# FOC_DRV8323.net
KiCad netlist of a schematic drawn in Altium Designer
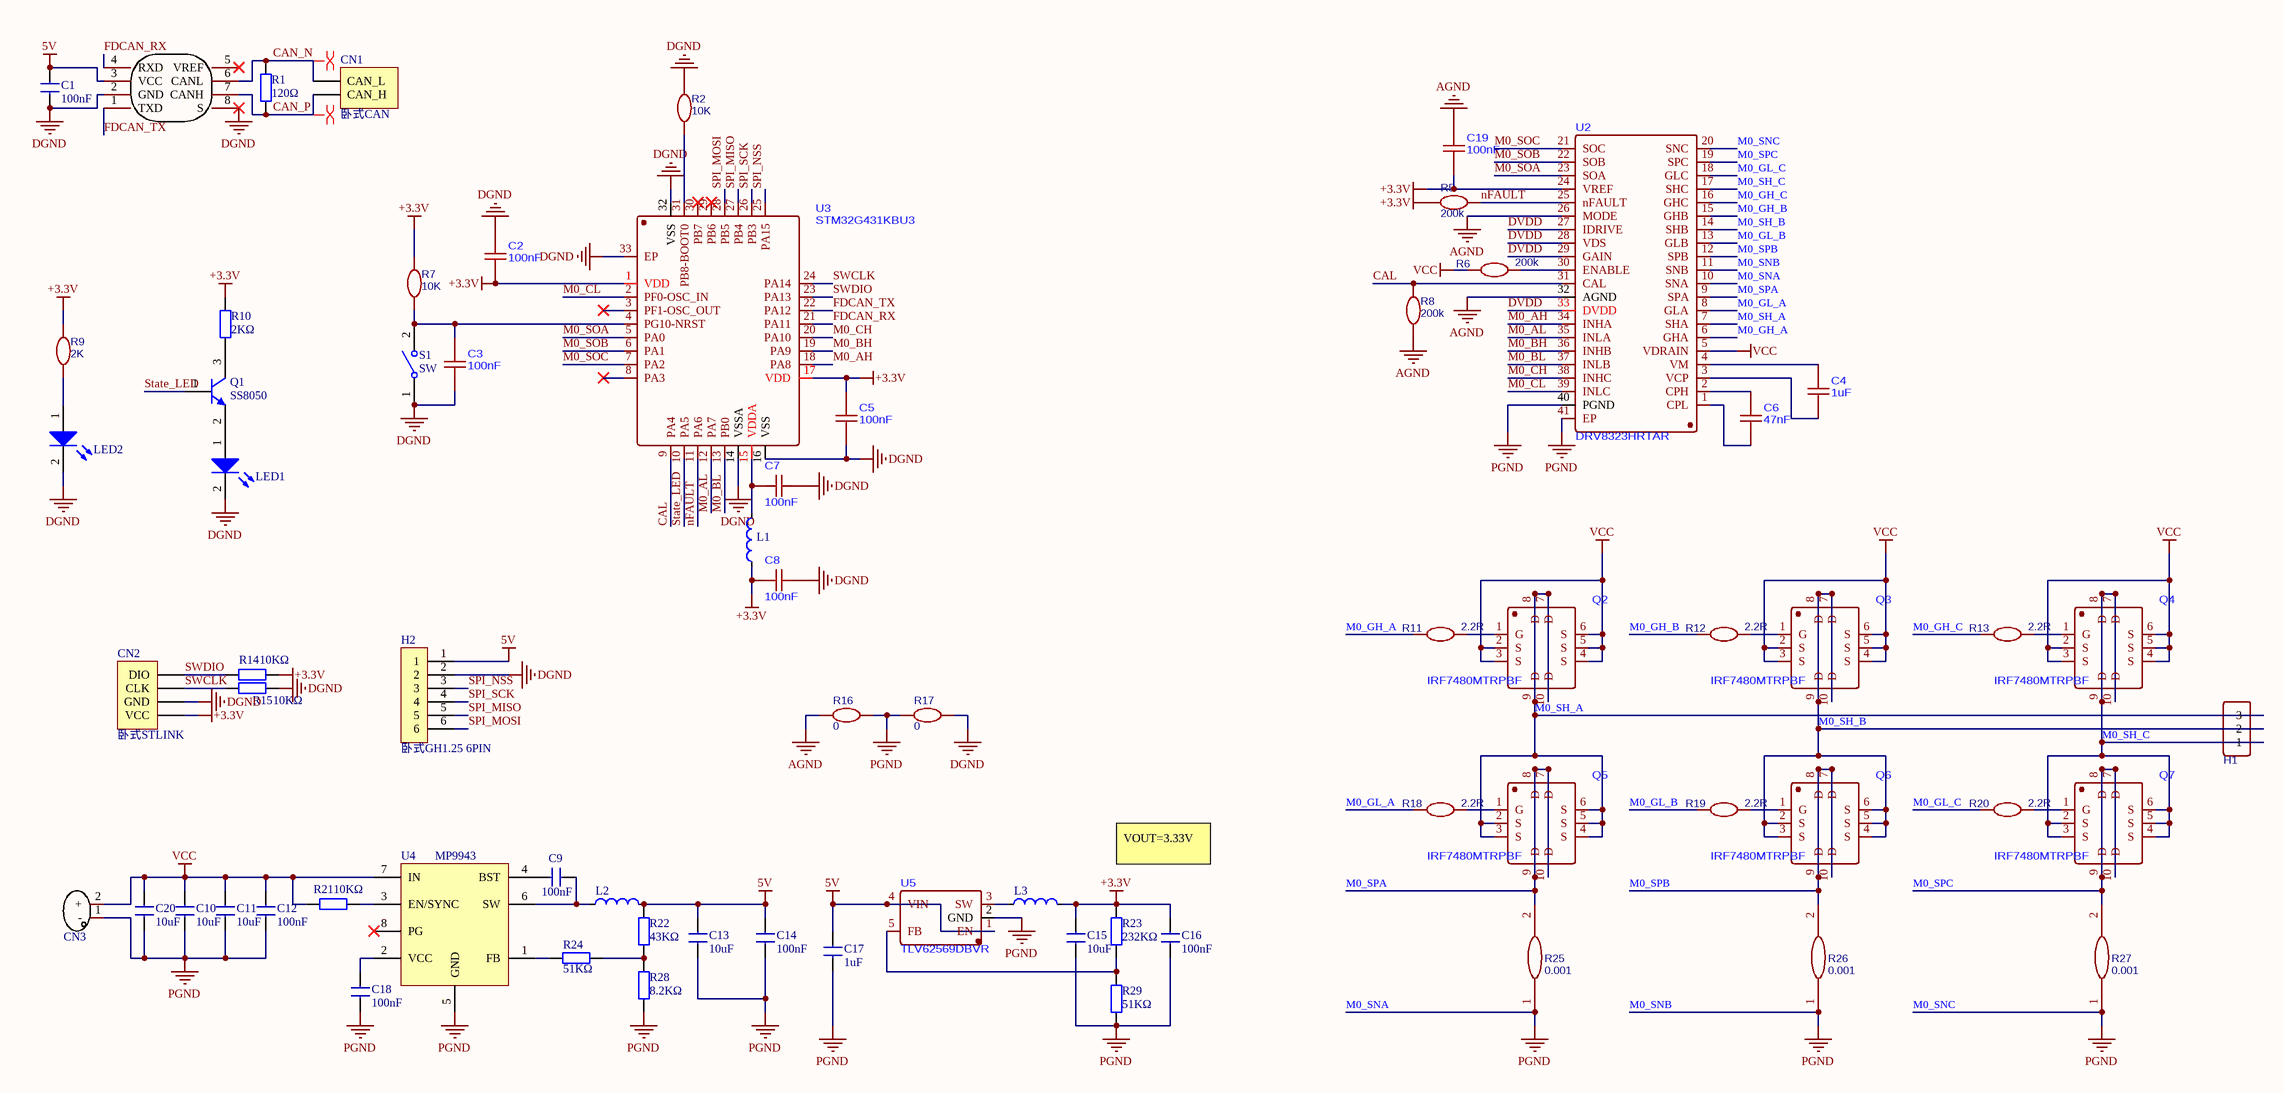
[diagram p0: FOC_DRV8323.SchDoc]

(export (version "E")
  (design (tool "Eeschema 10.0.6"))
  (components
    (comp (ref "C1")
      (value "100nF")
      (footprint "c0402")
      (description "贴片电容0402")
      (libsource (lib "Integrated_Library1") (part "0402贴片电容"))
    )
    (comp (ref "C2") (value "100nF") (footprint "c0402") (libsource (lib "PETO") (part "CC0201JRX7R9BB101")))
    (comp (ref "C3") (value "100nF") (footprint "c0402") (libsource (lib "PETO") (part "CC0201JRX7R9BB101")))
    (comp (ref "C4") (value "1uF") (footprint "c0402") (libsource (lib "PETO") (part "CC0201JRX7R9BB101")))
    (comp (ref "C5") (value "100nF") (footprint "c0402") (libsource (lib "PETO") (part "CC0201JRX7R9BB101")))
    (comp (ref "C6") (value "47nF") (footprint "c0402") (libsource (lib "PETO") (part "CC0201JRX7R9BB101")))
    (comp (ref "C7") (value "100nF") (footprint "c0402") (libsource (lib "PETO") (part "CC0201JRX7R9BB101")))
    (comp (ref "C8") (value "100nF") (footprint "c0402") (libsource (lib "PETO") (part "CC0201JRX7R9BB101")))
    (comp (ref "C9")
      (value "100nF")
      (footprint "c0402")
      (description "贴片电容0402")
      (libsource (lib "Integrated_Library1") (part "0402贴片电容"))
    )
    (comp (ref "C10")
      (value "10uF")
      (footprint "1210")
      (description "1210贴片电容")
      (libsource (lib "Integrated_Library1") (part "1210贴片电容"))
    )
    (comp (ref "C11")
      (value "10uF")
      (footprint "1210")
      (description "1210贴片电容")
      (libsource (lib "Integrated_Library1") (part "1210贴片电容"))
    )
    (comp (ref "C12")
      (value "100nF")
      (footprint "c0402")
      (description "贴片电容0402")
      (libsource (lib "Integrated_Library1") (part "0402贴片电容"))
    )
    (comp (ref "C13")
      (value "10uF")
      (footprint "1210")
      (description "1210贴片电容")
      (libsource (lib "Integrated_Library1") (part "1210贴片电容"))
    )
    (comp (ref "C14")
      (value "100nF")
      (footprint "c0402")
      (description "贴片电容0402")
      (libsource (lib "Integrated_Library1") (part "0402贴片电容"))
    )
    (comp (ref "C15")
      (value "10uF")
      (footprint "1210")
      (description "贴片电容0402")
      (libsource (lib "Integrated_Library1") (part "0402贴片电容"))
    )
    (comp (ref "C16")
      (value "100nF")
      (footprint "c0402")
      (description "贴片电容0402")
      (libsource (lib "Integrated_Library1") (part "0402贴片电容"))
    )
    (comp (ref "C17")
      (value "1uF")
      (footprint "c0402")
      (description "贴片电容0402")
      (libsource (lib "Integrated_Library1") (part "0402贴片电容"))
    )
    (comp (ref "C18")
      (value "100nF")
      (footprint "c0402")
      (description "贴片电容0402")
      (libsource (lib "Integrated_Library1") (part "0402贴片电容"))
    )
    (comp (ref "C19") (value "100nF") (footprint "c0402") (libsource (lib "PETO") (part "CC0201JRX7R9BB101")))
    (comp (ref "C20")
      (value "10uF")
      (footprint "1210")
      (description "1210贴片电容")
      (libsource (lib "Integrated_Library1") (part "1210贴片电容"))
    )
    (comp (ref "CN1")
      (value "卧式CAN")
      (footprint "GH1.25 2P 卧式")
      (fields (field (name "PUBLISHER") "Altium Limited"))
      (libsource (lib "Integrated_Library1") (part "卧式CAN"))
    )
    (comp (ref "CN2")
      (value "卧式STLINK")
      (footprint "CONN-SMD_4P-P1.25_GH1.25-4P")
      (libsource (lib "Integrated_Library1") (part "卧式STLINK"))
    )
    (comp (ref "CN3") (value "XT30_1") (footprint "XT30卧式焊盘") (libsource (lib "Schlib1") (part "XT30_1")))
    (comp (ref "H1")
      (value "MR30-M")
      (footprint "MR30")
      (fields (field (name "BOM_SUPPLIER PART") "C99873") (field (name "CONTRIBUTOR") "LCEDA_Lib"))
      (libsource (lib "altium-import") (part "root_2_MR30-M_"))
    )
    (comp (ref "H2")
      (value "卧式GH1.25 6PIN")
      (footprint "CONN-SMD_6P-P1.25_XYECONN_XY-GH1.25-6A61")
      (libsource (lib "En") (part "卧式GH1.25 6PIN"))
    )
    (comp (ref "L1")
      (value "1008屏蔽电感")
      (footprint "R0603")
      (libsource (lib "Integrated_Library1") (part "1008屏蔽电感"))
    )
    (comp (ref "L2")
      (value "1008屏蔽电感")
      (footprint "IND-SMD_L2.5-W2.0")
      (libsource (lib "Integrated_Library1") (part "1008屏蔽电感"))
    )
    (comp (ref "L3")
      (value "1008屏蔽电感")
      (footprint "IND-SMD_L2.5-W2.0")
      (libsource (lib "Integrated_Library1") (part "1008屏蔽电感"))
    )
    (comp (ref "LED1")
      (value "LED")
      (footprint "led0805")
      (description "0805贴片LED")
      (libsource (lib "Integrated_Library1") (part "0805贴片LED"))
    )
    (comp (ref "LED2")
      (value "LED")
      (footprint "led0805")
      (description "0805贴片LED")
      (libsource (lib "Integrated_Library1") (part "0805贴片LED"))
    )
    (comp (ref "Q1")
      (value "SS8050")
      (footprint "SOT-23-3_L2.9-W1.3-P1.90-LS2.4-BR")
      (description "三极管")
      (libsource (lib "Integrated_Library1") (part "2N2222"))
    )
    (comp (ref "Q2")
      (value "IRF7480MTRPBF")
      (footprint "TRS-SMD_IRF7480MTRPBF")
      (libsource (lib "FOC_DRV8301") (part "IRF7480MTRPBF"))
    )
    (comp (ref "Q3")
      (value "IRF7480MTRPBF")
      (footprint "TRS-SMD_IRF7480MTRPBF")
      (libsource (lib "FOC_DRV8301") (part "IRF7480MTRPBF"))
    )
    (comp (ref "Q4")
      (value "IRF7480MTRPBF")
      (footprint "TRS-SMD_IRF7480MTRPBF")
      (libsource (lib "FOC_DRV8301") (part "IRF7480MTRPBF"))
    )
    (comp (ref "Q5")
      (value "IRF7480MTRPBF")
      (footprint "TRS-SMD_IRF7480MTRPBF")
      (libsource (lib "FOC_DRV8301") (part "IRF7480MTRPBF"))
    )
    (comp (ref "Q6")
      (value "IRF7480MTRPBF")
      (footprint "TRS-SMD_IRF7480MTRPBF")
      (libsource (lib "FOC_DRV8301") (part "IRF7480MTRPBF"))
    )
    (comp (ref "Q7")
      (value "IRF7480MTRPBF")
      (footprint "TRS-SMD_IRF7480MTRPBF")
      (libsource (lib "FOC_DRV8301") (part "IRF7480MTRPBF"))
    )
    (comp (ref "R1")
      (value "120Ω")
      (footprint "R0402")
      (description "0402贴片电阻")
      (libsource (lib "Integrated_Library1") (part "0402贴片电阻"))
    )
    (comp (ref "R2")
      (value "10K")
      (footprint "R0402")
      (fields
        (field (name "BOM_MANUFACTURER PART") "0603WAJ022JT5E")
        (field (name "BOM_SUPPLIER PART") "C25226")
      )
      (libsource (lib "altium-import") (part "root_3_2.2R_"))
    )
    (comp (ref "R5")
      (value "200k")
      (footprint "R0402")
      (fields
        (field (name "BOM_MANUFACTURER PART") "0603WAJ022JT5E")
        (field (name "BOM_SUPPLIER PART") "C25226")
      )
      (libsource (lib "altium-import") (part "root_0_2.2R_"))
    )
    (comp (ref "R6")
      (value "200k")
      (footprint "R0402")
      (fields
        (field (name "BOM_MANUFACTURER PART") "0603WAJ022JT5E")
        (field (name "BOM_SUPPLIER PART") "C25226")
      )
      (libsource (lib "altium-import") (part "root_2_2.2R_"))
    )
    (comp (ref "R7")
      (value "10K")
      (footprint "R0402")
      (fields
        (field (name "BOM_MANUFACTURER PART") "0603WAJ022JT5E")
        (field (name "BOM_SUPPLIER PART") "C25226")
      )
      (libsource (lib "altium-import") (part "root_3_2.2R_"))
    )
    (comp (ref "R8")
      (value "200k")
      (footprint "R0402")
      (fields
        (field (name "BOM_MANUFACTURER PART") "0603WAJ022JT5E")
        (field (name "BOM_SUPPLIER PART") "C25226")
      )
      (libsource (lib "altium-import") (part "root_3_2.2R_"))
    )
    (comp (ref "R9")
      (value "2K")
      (footprint "R0402")
      (fields
        (field (name "BOM_MANUFACTURER PART") "0603WAJ022JT5E")
        (field (name "BOM_SUPPLIER PART") "C25226")
      )
      (libsource (lib "altium-import") (part "root_3_2.2R_"))
    )
    (comp (ref "R10")
      (value "2KΩ")
      (footprint "R0402")
      (description "0402贴片电阻")
      (libsource (lib "Integrated_Library1") (part "0402贴片电阻"))
    )
    (comp (ref "R11")
      (value "2.2R")
      (footprint "R0402")
      (fields
        (field (name "BOM_MANUFACTURER PART") "0603WAJ022JT5E")
        (field (name "BOM_SUPPLIER PART") "C25226")
      )
      (libsource (lib "altium-import") (part "root_2_2.2R_"))
    )
    (comp (ref "R12")
      (value "2.2R")
      (footprint "R0402")
      (fields
        (field (name "BOM_MANUFACTURER PART") "0603WAJ022JT5E")
        (field (name "BOM_SUPPLIER PART") "C25226")
      )
      (libsource (lib "altium-import") (part "root_2_2.2R_"))
    )
    (comp (ref "R13")
      (value "2.2R")
      (footprint "R0402")
      (fields
        (field (name "BOM_MANUFACTURER PART") "0603WAJ022JT5E")
        (field (name "BOM_SUPPLIER PART") "C25226")
      )
      (libsource (lib "altium-import") (part "root_2_2.2R_"))
    )
    (comp (ref "R14")
      (value "10KΩ")
      (footprint "R0402")
      (description "0402贴片电阻")
      (libsource (lib "") (part "0402贴片电阻_4"))
    )
    (comp (ref "R15")
      (value "10KΩ")
      (footprint "R0402")
      (description "0402贴片电阻")
      (libsource (lib "") (part "0402贴片电阻_3"))
    )
    (comp (ref "R16")
      (value "0")
      (footprint "R0402")
      (fields
        (field (name "BOM_MANUFACTURER PART") "0603WAJ022JT5E")
        (field (name "BOM_SUPPLIER PART") "C25226")
      )
      (libsource (lib "altium-import") (part "root_0_2.2R_"))
    )
    (comp (ref "R17")
      (value "0")
      (footprint "R0402")
      (fields
        (field (name "BOM_MANUFACTURER PART") "0603WAJ022JT5E")
        (field (name "BOM_SUPPLIER PART") "C25226")
      )
      (libsource (lib "altium-import") (part "root_0_2.2R_"))
    )
    (comp (ref "R18")
      (value "2.2R")
      (footprint "R0402")
      (fields
        (field (name "BOM_MANUFACTURER PART") "0603WAJ022JT5E")
        (field (name "BOM_SUPPLIER PART") "C25226")
      )
      (libsource (lib "altium-import") (part "root_2_2.2R_"))
    )
    (comp (ref "R19")
      (value "2.2R")
      (footprint "R0402")
      (fields
        (field (name "BOM_MANUFACTURER PART") "0603WAJ022JT5E")
        (field (name "BOM_SUPPLIER PART") "C25226")
      )
      (libsource (lib "altium-import") (part "root_2_2.2R_"))
    )
    (comp (ref "R20")
      (value "2.2R")
      (footprint "R0402")
      (fields
        (field (name "BOM_MANUFACTURER PART") "0603WAJ022JT5E")
        (field (name "BOM_SUPPLIER PART") "C25226")
      )
      (libsource (lib "altium-import") (part "root_2_2.2R_"))
    )
    (comp (ref "R21")
      (value "10KΩ")
      (footprint "R0402")
      (description "0402贴片电阻")
      (libsource (lib "") (part "0402贴片电阻_2"))
    )
    (comp (ref "R22")
      (value "43KΩ")
      (footprint "R0402")
      (description "0402贴片电阻")
      (libsource (lib "") (part "0402贴片电阻_1"))
    )
    (comp (ref "R23")
      (value "232KΩ")
      (footprint "R0402")
      (description "0402贴片电阻")
      (libsource (lib "") (part "0402贴片电阻_1"))
    )
    (comp (ref "R24")
      (value "51KΩ")
      (footprint "R0402")
      (description "0402贴片电阻")
      (libsource (lib "") (part "0402贴片电阻_2"))
    )
    (comp (ref "R25")
      (value "0.001")
      (footprint "R0612")
      (fields
        (field (name "BOM_SUPPLIER PART") "C2681067")
        (field (name "BOM_MANUFACTURER PART") "LR2512-23R0005J4")
        (field (name "CONTRIBUTOR") "LCSC")
      )
      (libsource (lib "altium-import") (part "root_1_0.0005_"))
    )
    (comp (ref "R26")
      (value "0.001")
      (footprint "R0612")
      (fields
        (field (name "BOM_SUPPLIER PART") "C2681067")
        (field (name "BOM_MANUFACTURER PART") "LR2512-23R0005J4")
        (field (name "CONTRIBUTOR") "LCSC")
      )
      (libsource (lib "altium-import") (part "root_1_0.0005_"))
    )
    (comp (ref "R27")
      (value "0.001")
      (footprint "R0612")
      (fields
        (field (name "BOM_SUPPLIER PART") "C2681067")
        (field (name "BOM_MANUFACTURER PART") "LR2512-23R0005J4")
        (field (name "CONTRIBUTOR") "LCSC")
      )
      (libsource (lib "altium-import") (part "root_1_0.0005_"))
    )
    (comp (ref "R28")
      (value "8.2KΩ")
      (footprint "R0402")
      (description "0402贴片电阻")
      (libsource (lib "") (part "0402贴片电阻_1"))
    )
    (comp (ref "R29")
      (value "51KΩ")
      (footprint "R0402")
      (description "0402贴片电阻")
      (libsource (lib "") (part "0402贴片电阻_1"))
    )
    (comp (ref "S1")
      (value "SW")
      (footprint "KEY_SMD")
      (description "开关")
      (libsource (lib "Integrated_Library1") (part "SW"))
    )
    (comp (ref "U1")
      (value "SN65HVD1050DR")
      (footprint "SOIC-8_L4.9-W3.9-P1.27-LS6.0-BL")
      (description "CAN芯片")
      (fields (field (name "MANUFACTURER") "TI(德州仪器)"))
      (libsource (lib "Integrated_Library1") (part "SN65HVD1050DR"))
    )
    (comp (ref "U2")
      (value "DRV8323HRTAR")
      (footprint "QFN-40_L6.0-W6.0-P0.50-BL-EP4.5")
      (libsource (lib "FOC_DRV8323") (part "DRV8323HRTAR"))
    )
    (comp (ref "U3")
      (value "STM32G431KBU3")
      (footprint "UFQFPN-32_L5.0-W5.0-P0.50-BL-EP3.5")
      (libsource (lib "FOC_DRV8323") (part "STM32G431KBU3"))
    )
    (comp (ref "U4")
      (value "MP9943")
      (footprint "QFN-8 3x3")
      (libsource (lib "Integrated_Library1") (part "MP9943"))
    )
    (comp (ref "U5")
      (value "TLV62569DBVR")
      (footprint "SOT-23-5_L3.0-W1.7-P0.95-LS2.8-BR")
      (libsource (lib "FOC_DRV8323") (part "TLV62569DBVR"))
    )
  )
  (nets
    (net (code "1") (name "+3.3V") (class "Default")
      (node (ref "C15") (pin "2") (pinfunction "2_2") (pintype "passive"))
      (node (ref "C16") (pin "2") (pinfunction "2_2") (pintype "passive"))
      (node (ref "C19") (pin "1") (pinfunction "1_1") (pintype "passive"))
      (node (ref "C2") (pin "2") (pinfunction "2_2") (pintype "passive"))
      (node (ref "C5") (pin "2") (pinfunction "2_2") (pintype "passive"))
      (node (ref "C8") (pin "2") (pinfunction "2_2") (pintype "passive"))
      (node (ref "CN2") (pin "1") (pinfunction "VCC_1") (pintype "passive"))
      (node (ref "L1") (pin "1") (pinfunction "1_1") (pintype "passive"))
      (node (ref "L3") (pin "2") (pinfunction "2_2") (pintype "passive"))
      (node (ref "R10") (pin "2") (pinfunction "2_2") (pintype "passive"))
      (node (ref "R14") (pin "1") (pinfunction "1_1") (pintype "passive"))
      (node (ref "R23") (pin "2") (pinfunction "2_2") (pintype "passive"))
      (node (ref "R5") (pin "1") (pinfunction "1_1") (pintype "passive"))
      (node (ref "R7") (pin "1") (pinfunction "1_1") (pintype "passive"))
      (node (ref "R9") (pin "1") (pinfunction "1_1") (pintype "passive"))
      (node (ref "U2") (pin "24") (pinfunction "VREF_24") (pintype "passive"))
      (node (ref "U3") (pin "1") (pinfunction "VDD_1") (pintype "passive"))
      (node (ref "U3") (pin "17") (pinfunction "VDD_17") (pintype "passive"))
    )
    (net (code "2") (name "/CAL") (class "Default")
      (node (ref "R8") (pin "1") (pinfunction "1_1") (pintype "passive"))
      (node (ref "U2") (pin "31") (pinfunction "CAL_31") (pintype "passive"))
      (node (ref "U3") (pin "9") (pinfunction "PA4_9") (pintype "passive"))
    )
    (net (code "3") (name "/CAN_N") (class "Default")
      (node (ref "CN1") (pin "2") (pinfunction "CAN_L_2") (pintype "passive"))
      (node (ref "R1") (pin "2") (pinfunction "2_2") (pintype "passive"))
      (node (ref "U1") (pin "6") (pinfunction "CANL_6") (pintype "passive"))
    )
    (net (code "4") (name "/CAN_P") (class "Default")
      (node (ref "CN1") (pin "1") (pinfunction "CAN_H_1") (pintype "passive"))
      (node (ref "R1") (pin "1") (pinfunction "1_1") (pintype "passive"))
      (node (ref "U1") (pin "7") (pinfunction "CANH_7") (pintype "passive"))
    )
    (net (code "5") (name "/DVDD") (class "Default")
      (node (ref "U2") (pin "27") (pinfunction "IDRIVE_27") (pintype "passive"))
      (node (ref "U2") (pin "28") (pinfunction "VDS_28") (pintype "passive"))
      (node (ref "U2") (pin "29") (pinfunction "GAIN_29") (pintype "passive"))
      (node (ref "U2") (pin "33") (pinfunction "DVDD_33") (pintype "passive"))
    )
    (net (code "6") (name "/FDCAN_RX") (class "Default")
      (node (ref "U1") (pin "4") (pinfunction "RXD_4") (pintype "passive"))
      (node (ref "U3") (pin "21") (pinfunction "PA11_21") (pintype "passive"))
    )
    (net (code "7") (name "/FDCAN_TX") (class "Default")
      (node (ref "U1") (pin "1") (pinfunction "TXD_1") (pintype "passive"))
      (node (ref "U3") (pin "22") (pinfunction "PA12_22") (pintype "passive"))
    )
    (net (code "8") (name "/M0_AH") (class "Default")
      (node (ref "U2") (pin "34") (pinfunction "INHA_34") (pintype "passive"))
      (node (ref "U3") (pin "18") (pinfunction "PA8_18") (pintype "passive"))
    )
    (net (code "9") (name "/M0_AL") (class "Default")
      (node (ref "U2") (pin "35") (pinfunction "INLA_35") (pintype "passive"))
      (node (ref "U3") (pin "12") (pinfunction "PA7_12") (pintype "passive"))
    )
    (net (code "10") (name "/M0_BH") (class "Default")
      (node (ref "U2") (pin "36") (pinfunction "INHB_36") (pintype "passive"))
      (node (ref "U3") (pin "19") (pinfunction "PA9_19") (pintype "passive"))
    )
    (net (code "11") (name "/M0_BL") (class "Default")
      (node (ref "U2") (pin "37") (pinfunction "INLB_37") (pintype "passive"))
      (node (ref "U3") (pin "13") (pinfunction "PB0_13") (pintype "passive"))
    )
    (net (code "12") (name "/M0_CH") (class "Default")
      (node (ref "U2") (pin "38") (pinfunction "INHC_38") (pintype "passive"))
      (node (ref "U3") (pin "20") (pinfunction "PA10_20") (pintype "passive"))
    )
    (net (code "13") (name "/M0_CL") (class "Default")
      (node (ref "U2") (pin "39") (pinfunction "INLC_39") (pintype "passive"))
      (node (ref "U3") (pin "2") (pinfunction "PF0-OSC_IN_2") (pintype "passive"))
    )
    (net (code "14") (name "/M0_GH_A") (class "Default")
      (node (ref "R11") (pin "2") (pinfunction "2_2") (pintype "passive"))
      (node (ref "U2") (pin "6") (pinfunction "GHA_6") (pintype "passive"))
    )
    (net (code "15") (name "/M0_GH_B") (class "Default")
      (node (ref "R12") (pin "2") (pinfunction "2_2") (pintype "passive"))
      (node (ref "U2") (pin "15") (pinfunction "GHB_15") (pintype "passive"))
    )
    (net (code "16") (name "/M0_GH_C") (class "Default")
      (node (ref "R13") (pin "2") (pinfunction "2_2") (pintype "passive"))
      (node (ref "U2") (pin "16") (pinfunction "GHC_16") (pintype "passive"))
    )
    (net (code "17") (name "/M0_GL_A") (class "Default")
      (node (ref "R18") (pin "2") (pinfunction "2_2") (pintype "passive"))
      (node (ref "U2") (pin "8") (pinfunction "GLA_8") (pintype "passive"))
    )
    (net (code "18") (name "/M0_GL_B") (class "Default")
      (node (ref "R19") (pin "2") (pinfunction "2_2") (pintype "passive"))
      (node (ref "U2") (pin "13") (pinfunction "GLB_13") (pintype "passive"))
    )
    (net (code "19") (name "/M0_GL_C") (class "Default")
      (node (ref "R20") (pin "2") (pinfunction "2_2") (pintype "passive"))
      (node (ref "U2") (pin "18") (pinfunction "GLC_18") (pintype "passive"))
    )
    (net (code "20") (name "/M0_SH_A") (class "Default")
      (node (ref "H1") (pin "3") (pinfunction "3_3") (pintype "passive"))
      (node (ref "Q2") (pin "10") (pinfunction "D_10") (pintype "passive"))
      (node (ref "Q2") (pin "7") (pinfunction "D_7") (pintype "passive"))
      (node (ref "Q2") (pin "8") (pinfunction "D_8") (pintype "passive"))
      (node (ref "Q2") (pin "9") (pinfunction "D_9") (pintype "passive"))
      (node (ref "Q5") (pin "2") (pinfunction "S_2") (pintype "passive"))
      (node (ref "Q5") (pin "3") (pinfunction "S_3") (pintype "passive"))
      (node (ref "Q5") (pin "4") (pinfunction "S_4") (pintype "passive"))
      (node (ref "Q5") (pin "5") (pinfunction "S_5") (pintype "passive"))
      (node (ref "Q5") (pin "6") (pinfunction "S_6") (pintype "passive"))
      (node (ref "U2") (pin "7") (pinfunction "SHA_7") (pintype "passive"))
    )
    (net (code "21") (name "/M0_SH_B") (class "Default")
      (node (ref "H1") (pin "2") (pinfunction "2_2") (pintype "passive"))
      (node (ref "Q3") (pin "10") (pinfunction "D_10") (pintype "passive"))
      (node (ref "Q3") (pin "7") (pinfunction "D_7") (pintype "passive"))
      (node (ref "Q3") (pin "8") (pinfunction "D_8") (pintype "passive"))
      (node (ref "Q3") (pin "9") (pinfunction "D_9") (pintype "passive"))
      (node (ref "Q6") (pin "2") (pinfunction "S_2") (pintype "passive"))
      (node (ref "Q6") (pin "3") (pinfunction "S_3") (pintype "passive"))
      (node (ref "Q6") (pin "4") (pinfunction "S_4") (pintype "passive"))
      (node (ref "Q6") (pin "5") (pinfunction "S_5") (pintype "passive"))
      (node (ref "Q6") (pin "6") (pinfunction "S_6") (pintype "passive"))
      (node (ref "U2") (pin "14") (pinfunction "SHB_14") (pintype "passive"))
    )
    (net (code "22") (name "/M0_SH_C") (class "Default")
      (node (ref "H1") (pin "1") (pinfunction "1_1") (pintype "passive"))
      (node (ref "Q4") (pin "10") (pinfunction "D_10") (pintype "passive"))
      (node (ref "Q4") (pin "7") (pinfunction "D_7") (pintype "passive"))
      (node (ref "Q4") (pin "8") (pinfunction "D_8") (pintype "passive"))
      (node (ref "Q4") (pin "9") (pinfunction "D_9") (pintype "passive"))
      (node (ref "Q7") (pin "2") (pinfunction "S_2") (pintype "passive"))
      (node (ref "Q7") (pin "3") (pinfunction "S_3") (pintype "passive"))
      (node (ref "Q7") (pin "4") (pinfunction "S_4") (pintype "passive"))
      (node (ref "Q7") (pin "5") (pinfunction "S_5") (pintype "passive"))
      (node (ref "Q7") (pin "6") (pinfunction "S_6") (pintype "passive"))
      (node (ref "U2") (pin "17") (pinfunction "SHC_17") (pintype "passive"))
    )
    (net (code "23") (name "/M0_SOA") (class "Default")
      (node (ref "U2") (pin "23") (pinfunction "SOA_23") (pintype "passive"))
      (node (ref "U3") (pin "5") (pinfunction "PA0_5") (pintype "passive"))
    )
    (net (code "24") (name "/M0_SOB") (class "Default")
      (node (ref "U2") (pin "22") (pinfunction "SOB_22") (pintype "passive"))
      (node (ref "U3") (pin "6") (pinfunction "PA1_6") (pintype "passive"))
    )
    (net (code "25") (name "/M0_SOC") (class "Default")
      (node (ref "U2") (pin "21") (pinfunction "SOC_21") (pintype "passive"))
      (node (ref "U3") (pin "7") (pinfunction "PA2_7") (pintype "passive"))
    )
    (net (code "26") (name "/M0_SPA") (class "Default")
      (node (ref "Q5") (pin "10") (pinfunction "D_10") (pintype "passive"))
      (node (ref "Q5") (pin "7") (pinfunction "D_7") (pintype "passive"))
      (node (ref "Q5") (pin "8") (pinfunction "D_8") (pintype "passive"))
      (node (ref "Q5") (pin "9") (pinfunction "D_9") (pintype "passive"))
      (node (ref "R25") (pin "2") (pinfunction "2_2") (pintype "passive"))
      (node (ref "U2") (pin "9") (pinfunction "SPA_9") (pintype "passive"))
    )
    (net (code "27") (name "/M0_SPB") (class "Default")
      (node (ref "Q6") (pin "10") (pinfunction "D_10") (pintype "passive"))
      (node (ref "Q6") (pin "7") (pinfunction "D_7") (pintype "passive"))
      (node (ref "Q6") (pin "8") (pinfunction "D_8") (pintype "passive"))
      (node (ref "Q6") (pin "9") (pinfunction "D_9") (pintype "passive"))
      (node (ref "R26") (pin "2") (pinfunction "2_2") (pintype "passive"))
      (node (ref "U2") (pin "12") (pinfunction "SPB_12") (pintype "passive"))
    )
    (net (code "28") (name "/M0_SPC") (class "Default")
      (node (ref "Q7") (pin "10") (pinfunction "D_10") (pintype "passive"))
      (node (ref "Q7") (pin "7") (pinfunction "D_7") (pintype "passive"))
      (node (ref "Q7") (pin "8") (pinfunction "D_8") (pintype "passive"))
      (node (ref "Q7") (pin "9") (pinfunction "D_9") (pintype "passive"))
      (node (ref "R27") (pin "2") (pinfunction "2_2") (pintype "passive"))
      (node (ref "U2") (pin "19") (pinfunction "SPC_19") (pintype "passive"))
    )
    (net (code "29") (name "/SPI_MISO") (class "Default")
      (node (ref "H2") (pin "5") (pinfunction "5_5") (pintype "passive"))
      (node (ref "U3") (pin "27") (pinfunction "PB4_27") (pintype "passive"))
    )
    (net (code "30") (name "/SPI_MOSI") (class "Default")
      (node (ref "H2") (pin "6") (pinfunction "6_6") (pintype "passive"))
      (node (ref "U3") (pin "28") (pinfunction "PB5_28") (pintype "passive"))
    )
    (net (code "31") (name "/SPI_NSS") (class "Default")
      (node (ref "H2") (pin "3") (pinfunction "3_3") (pintype "passive"))
      (node (ref "U3") (pin "25") (pinfunction "PA15_25") (pintype "passive"))
    )
    (net (code "32") (name "/SPI_SCK") (class "Default")
      (node (ref "H2") (pin "4") (pinfunction "4_4") (pintype "passive"))
      (node (ref "U3") (pin "26") (pinfunction "PB3_26") (pintype "passive"))
    )
    (net (code "33") (name "/SWCLK") (class "Default")
      (node (ref "CN2") (pin "3") (pinfunction "CLK_3") (pintype "passive"))
      (node (ref "R15") (pin "1") (pinfunction "1_1") (pintype "passive"))
      (node (ref "U3") (pin "24") (pinfunction "PA14_24") (pintype "passive"))
    )
    (net (code "34") (name "/SWDIO") (class "Default")
      (node (ref "CN2") (pin "4") (pinfunction "DIO_4") (pintype "passive"))
      (node (ref "R14") (pin "2") (pinfunction "2_2") (pintype "passive"))
      (node (ref "U3") (pin "23") (pinfunction "PA13_23") (pintype "passive"))
    )
    (net (code "35") (name "/State_LED") (class "Default")
      (node (ref "Q1") (pin "1") (pinfunction "B_1") (pintype "passive"))
      (node (ref "U3") (pin "10") (pinfunction "PA5_10") (pintype "passive"))
    )
    (net (code "36") (name "/nFAULT") (class "Default")
      (node (ref "R5") (pin "2") (pinfunction "2_2") (pintype "passive"))
      (node (ref "U2") (pin "25") (pinfunction "nFAULT_25") (pintype "passive"))
      (node (ref "U3") (pin "11") (pinfunction "PA6_11") (pintype "passive"))
    )
    (net (code "37") (name "5V") (class "Default")
      (node (ref "C1") (pin "2") (pinfunction "2_2") (pintype "passive"))
      (node (ref "C13") (pin "2") (pinfunction "2_2") (pintype "passive"))
      (node (ref "C14") (pin "2") (pinfunction "2_2") (pintype "passive"))
      (node (ref "C17") (pin "2") (pinfunction "2_2") (pintype "passive"))
      (node (ref "H2") (pin "1") (pinfunction "1_1") (pintype "passive"))
      (node (ref "L2") (pin "2") (pinfunction "2_2") (pintype "passive"))
      (node (ref "R22") (pin "2") (pinfunction "2_2") (pintype "passive"))
      (node (ref "U1") (pin "3") (pinfunction "VCC_3") (pintype "passive"))
      (node (ref "U5") (pin "1") (pinfunction "EN_1") (pintype "passive"))
      (node (ref "U5") (pin "4") (pinfunction "VIN_4") (pintype "passive"))
    )
    (net (code "38") (name "AGND") (class "Default")
      (node (ref "C19") (pin "2") (pinfunction "2_2") (pintype "passive"))
      (node (ref "R16") (pin "1") (pinfunction "1_1") (pintype "passive"))
      (node (ref "R8") (pin "2") (pinfunction "2_2") (pintype "passive"))
      (node (ref "U2") (pin "26") (pinfunction "MODE_26") (pintype "passive"))
      (node (ref "U2") (pin "32") (pinfunction "AGND_32") (pintype "passive"))
    )
    (net (code "39") (name "DGND") (class "Default")
      (node (ref "C1") (pin "1") (pinfunction "1_1") (pintype "passive"))
      (node (ref "C2") (pin "1") (pinfunction "1_1") (pintype "passive"))
      (node (ref "C3") (pin "1") (pinfunction "1_1") (pintype "passive"))
      (node (ref "C5") (pin "1") (pinfunction "1_1") (pintype "passive"))
      (node (ref "C7") (pin "1") (pinfunction "1_1") (pintype "passive"))
      (node (ref "C8") (pin "1") (pinfunction "1_1") (pintype "passive"))
      (node (ref "CN2") (pin "2") (pinfunction "GND_2") (pintype "passive"))
      (node (ref "H2") (pin "2") (pinfunction "2_2") (pintype "passive"))
      (node (ref "LED1") (pin "2") (pinfunction "K_2") (pintype "passive"))
      (node (ref "LED2") (pin "2") (pinfunction "K_2") (pintype "passive"))
      (node (ref "R15") (pin "2") (pinfunction "2_2") (pintype "passive"))
      (node (ref "R17") (pin "2") (pinfunction "2_2") (pintype "passive"))
      (node (ref "R2") (pin "1") (pinfunction "1_1") (pintype "passive"))
      (node (ref "S1") (pin "1") (pinfunction "COMMON_1") (pintype "passive"))
      (node (ref "U1") (pin "2") (pinfunction "GND_2") (pintype "passive"))
      (node (ref "U1") (pin "8") (pinfunction "S_8") (pintype "passive"))
      (node (ref "U3") (pin "14") (pinfunction "VSSA_14") (pintype "passive"))
      (node (ref "U3") (pin "16") (pinfunction "VSS_16") (pintype "passive"))
      (node (ref "U3") (pin "32") (pinfunction "VSS_32") (pintype "passive"))
      (node (ref "U3") (pin "33") (pinfunction "EP_33") (pintype "passive"))
    )
    (net (code "40") (name "Net-(LED1-A)") (class "Default")
      (node (ref "LED1") (pin "1") (pinfunction "A_1") (pintype "passive"))
      (node (ref "Q1") (pin "2") (pinfunction "E_2") (pintype "passive"))
    )
    (net (code "41") (name "Net-(LED2-A)") (class "Default")
      (node (ref "LED2") (pin "1") (pinfunction "A_1") (pintype "passive"))
      (node (ref "R9") (pin "2") (pinfunction "2_2") (pintype "passive"))
    )
    (net (code "42") (name "Net-(Q1-C)") (class "Default")
      (node (ref "Q1") (pin "3") (pinfunction "C_3") (pintype "passive"))
      (node (ref "R10") (pin "1") (pinfunction "1_1") (pintype "passive"))
    )
    (net (code "43") (name "Net-(Q2-G)") (class "Default")
      (node (ref "Q2") (pin "1") (pinfunction "G_1") (pintype "passive"))
      (node (ref "R11") (pin "1") (pinfunction "1_1") (pintype "passive"))
    )
    (net (code "44") (name "Net-(Q3-G)") (class "Default")
      (node (ref "Q3") (pin "1") (pinfunction "G_1") (pintype "passive"))
      (node (ref "R12") (pin "1") (pinfunction "1_1") (pintype "passive"))
    )
    (net (code "45") (name "Net-(Q4-G)") (class "Default")
      (node (ref "Q4") (pin "1") (pinfunction "G_1") (pintype "passive"))
      (node (ref "R13") (pin "1") (pinfunction "1_1") (pintype "passive"))
    )
    (net (code "46") (name "Net-(Q5-G)") (class "Default")
      (node (ref "Q5") (pin "1") (pinfunction "G_1") (pintype "passive"))
      (node (ref "R18") (pin "1") (pinfunction "1_1") (pintype "passive"))
    )
    (net (code "47") (name "Net-(Q6-G)") (class "Default")
      (node (ref "Q6") (pin "1") (pinfunction "G_1") (pintype "passive"))
      (node (ref "R19") (pin "1") (pinfunction "1_1") (pintype "passive"))
    )
    (net (code "48") (name "Net-(Q7-G)") (class "Default")
      (node (ref "Q7") (pin "1") (pinfunction "G_1") (pintype "passive"))
      (node (ref "R20") (pin "1") (pinfunction "1_1") (pintype "passive"))
    )
    (net (code "49") (name "Net-(R22-Pad1)") (class "Default")
      (node (ref "R22") (pin "1") (pinfunction "1_1") (pintype "passive"))
      (node (ref "R24") (pin "2") (pinfunction "2_2") (pintype "passive"))
      (node (ref "R28") (pin "2") (pinfunction "2_2") (pintype "passive"))
    )
    (net (code "50") (name "Net-(S1-NO)") (class "Default")
      (node (ref "C3") (pin "2") (pinfunction "2_2") (pintype "passive"))
      (node (ref "R7") (pin "2") (pinfunction "2_2") (pintype "passive"))
      (node (ref "S1") (pin "2") (pinfunction "NO_2") (pintype "passive"))
      (node (ref "U3") (pin "4") (pinfunction "PG10-NRST_4") (pintype "passive"))
    )
    (net (code "51") (name "Net-(U2-CPH)") (class "Default")
      (node (ref "C6") (pin "2") (pinfunction "2_2") (pintype "passive"))
      (node (ref "U2") (pin "2") (pinfunction "CPH_2") (pintype "passive"))
    )
    (net (code "52") (name "Net-(U2-CPL)") (class "Default")
      (node (ref "C6") (pin "1") (pinfunction "1_1") (pintype "passive"))
      (node (ref "U2") (pin "1") (pinfunction "CPL_1") (pintype "passive"))
    )
    (net (code "53") (name "Net-(U2-ENABLE)") (class "Default")
      (node (ref "R6") (pin "1") (pinfunction "1_1") (pintype "passive"))
      (node (ref "U2") (pin "30") (pinfunction "ENABLE_30") (pintype "passive"))
    )
    (net (code "54") (name "Net-(U2-VCP)") (class "Default")
      (node (ref "C4") (pin "1") (pinfunction "1_1") (pintype "passive"))
      (node (ref "U2") (pin "3") (pinfunction "VCP_3") (pintype "passive"))
    )
    (net (code "55") (name "Net-(U2-VM)") (class "Default")
      (node (ref "C4") (pin "2") (pinfunction "2_2") (pintype "passive"))
      (node (ref "U2") (pin "4") (pinfunction "VM_4") (pintype "passive"))
    )
    (net (code "56") (name "Net-(U3-PB8-BOOT0)") (class "Default")
      (node (ref "R2") (pin "2") (pinfunction "2_2") (pintype "passive"))
      (node (ref "U3") (pin "31") (pinfunction "PB8-BOOT0_31") (pintype "passive"))
    )
    (net (code "57") (name "Net-(U3-VDDA)") (class "Default")
      (node (ref "C7") (pin "2") (pinfunction "2_2") (pintype "passive"))
      (node (ref "L1") (pin "2") (pinfunction "2_2") (pintype "passive"))
      (node (ref "U3") (pin "15") (pinfunction "VDDA_15") (pintype "passive"))
    )
    (net (code "58") (name "Net-(U4-BST)") (class "Default")
      (node (ref "C9") (pin "1") (pinfunction "1_1") (pintype "passive"))
      (node (ref "U4") (pin "4") (pinfunction "BST_4") (pintype "passive"))
    )
    (net (code "59") (name "Net-(U4-EN{slash}SYNC)") (class "Default")
      (node (ref "R21") (pin "2") (pinfunction "2_2") (pintype "passive"))
      (node (ref "U4") (pin "3") (pinfunction "EN/SYNC_3") (pintype "passive"))
    )
    (net (code "60") (name "Net-(U4-FB)") (class "Default")
      (node (ref "R24") (pin "1") (pinfunction "1_1") (pintype "passive"))
      (node (ref "U4") (pin "1") (pinfunction "FB_1") (pintype "passive"))
    )
    (net (code "61") (name "Net-(U4-SW)") (class "Default")
      (node (ref "C9") (pin "2") (pinfunction "2_2") (pintype "passive"))
      (node (ref "L2") (pin "1") (pinfunction "1_1") (pintype "passive"))
      (node (ref "U4") (pin "6") (pinfunction "SW_6") (pintype "passive"))
    )
    (net (code "62") (name "Net-(U4-VCC)") (class "Default")
      (node (ref "C18") (pin "2") (pinfunction "2_2") (pintype "passive"))
      (node (ref "U4") (pin "2") (pinfunction "VCC_2") (pintype "passive"))
    )
    (net (code "63") (name "Net-(U5-FB)") (class "Default")
      (node (ref "R23") (pin "1") (pinfunction "1_1") (pintype "passive"))
      (node (ref "R29") (pin "2") (pinfunction "2_2") (pintype "passive"))
      (node (ref "U5") (pin "5") (pinfunction "FB_5") (pintype "passive"))
    )
    (net (code "64") (name "Net-(U5-SW)") (class "Default")
      (node (ref "L3") (pin "1") (pinfunction "1_1") (pintype "passive"))
      (node (ref "U5") (pin "3") (pinfunction "SW_3") (pintype "passive"))
    )
    (net (code "65") (name "PGND") (class "Default")
      (node (ref "C10") (pin "1") (pinfunction "1_1") (pintype "passive"))
      (node (ref "C11") (pin "1") (pinfunction "1_1") (pintype "passive"))
      (node (ref "C12") (pin "1") (pinfunction "1_1") (pintype "passive"))
      (node (ref "C13") (pin "1") (pinfunction "1_1") (pintype "passive"))
      (node (ref "C14") (pin "1") (pinfunction "1_1") (pintype "passive"))
      (node (ref "C15") (pin "1") (pinfunction "1_1") (pintype "passive"))
      (node (ref "C16") (pin "1") (pinfunction "1_1") (pintype "passive"))
      (node (ref "C17") (pin "1") (pinfunction "1_1") (pintype "passive"))
      (node (ref "C18") (pin "1") (pinfunction "1_1") (pintype "passive"))
      (node (ref "C20") (pin "1") (pinfunction "1_1") (pintype "passive"))
      (node (ref "CN3") (pin "1") (pinfunction "-_1") (pintype "passive"))
      (node (ref "R16") (pin "2") (pinfunction "2_2") (pintype "passive"))
      (node (ref "R17") (pin "1") (pinfunction "1_1") (pintype "passive"))
      (node (ref "R25") (pin "1") (pinfunction "1_1") (pintype "passive"))
      (node (ref "R26") (pin "1") (pinfunction "1_1") (pintype "passive"))
      (node (ref "R27") (pin "1") (pinfunction "1_1") (pintype "passive"))
      (node (ref "R28") (pin "1") (pinfunction "1_1") (pintype "passive"))
      (node (ref "R29") (pin "1") (pinfunction "1_1") (pintype "passive"))
      (node (ref "U2") (pin "10") (pinfunction "SNA_10") (pintype "passive"))
      (node (ref "U2") (pin "11") (pinfunction "SNB_11") (pintype "passive"))
      (node (ref "U2") (pin "20") (pinfunction "SNC_20") (pintype "passive"))
      (node (ref "U2") (pin "40") (pinfunction "PGND_40") (pintype "passive"))
      (node (ref "U2") (pin "41") (pinfunction "EP_41") (pintype "passive"))
      (node (ref "U4") (pin "5") (pinfunction "GND_5") (pintype "passive"))
      (node (ref "U5") (pin "2") (pinfunction "GND_2") (pintype "passive"))
    )
    (net (code "66") (name "VCC") (class "Default")
      (node (ref "C10") (pin "2") (pinfunction "2_2") (pintype "passive"))
      (node (ref "C11") (pin "2") (pinfunction "2_2") (pintype "passive"))
      (node (ref "C12") (pin "2") (pinfunction "2_2") (pintype "passive"))
      (node (ref "C20") (pin "2") (pinfunction "2_2") (pintype "passive"))
      (node (ref "CN3") (pin "2") (pinfunction "+_2") (pintype "passive"))
      (node (ref "Q2") (pin "2") (pinfunction "S_2") (pintype "passive"))
      (node (ref "Q2") (pin "3") (pinfunction "S_3") (pintype "passive"))
      (node (ref "Q2") (pin "4") (pinfunction "S_4") (pintype "passive"))
      (node (ref "Q2") (pin "5") (pinfunction "S_5") (pintype "passive"))
      (node (ref "Q2") (pin "6") (pinfunction "S_6") (pintype "passive"))
      (node (ref "Q3") (pin "2") (pinfunction "S_2") (pintype "passive"))
      (node (ref "Q3") (pin "3") (pinfunction "S_3") (pintype "passive"))
      (node (ref "Q3") (pin "4") (pinfunction "S_4") (pintype "passive"))
      (node (ref "Q3") (pin "5") (pinfunction "S_5") (pintype "passive"))
      (node (ref "Q3") (pin "6") (pinfunction "S_6") (pintype "passive"))
      (node (ref "Q4") (pin "2") (pinfunction "S_2") (pintype "passive"))
      (node (ref "Q4") (pin "3") (pinfunction "S_3") (pintype "passive"))
      (node (ref "Q4") (pin "4") (pinfunction "S_4") (pintype "passive"))
      (node (ref "Q4") (pin "5") (pinfunction "S_5") (pintype "passive"))
      (node (ref "Q4") (pin "6") (pinfunction "S_6") (pintype "passive"))
      (node (ref "R21") (pin "1") (pinfunction "1_1") (pintype "passive"))
      (node (ref "R6") (pin "2") (pinfunction "2_2") (pintype "passive"))
      (node (ref "U2") (pin "5") (pinfunction "VDRAIN_5") (pintype "passive"))
      (node (ref "U4") (pin "7") (pinfunction "IN_7") (pintype "passive"))
    )
    (net (code "67") (name "unconnected-(U1-VREF-Pad5)") (class "Default")
      (node (ref "U1") (pin "5") (pinfunction "VREF_5") (pintype "passive+no_connect"))
    )
    (net (code "68") (name "unconnected-(U3-PA3-Pad8)") (class "Default")
      (node (ref "U3") (pin "8") (pinfunction "PA3_8") (pintype "passive+no_connect"))
    )
    (net (code "69") (name "unconnected-(U3-PB6-Pad29)") (class "Default")
      (node (ref "U3") (pin "29") (pinfunction "PB6_29") (pintype "passive+no_connect"))
    )
    (net (code "70") (name "unconnected-(U3-PB7-Pad30)") (class "Default")
      (node (ref "U3") (pin "30") (pinfunction "PB7_30") (pintype "passive+no_connect"))
    )
    (net (code "71") (name "unconnected-(U3-PF1-OSC_OUT-Pad3)") (class "Default")
      (node (ref "U3") (pin "3") (pinfunction "PF1-OSC_OUT_3") (pintype "passive+no_connect"))
    )
    (net (code "72") (name "unconnected-(U4-PG-Pad8)") (class "Default")
      (node (ref "U4") (pin "8") (pinfunction "PG_8") (pintype "passive+no_connect"))
    )
  )
)
